# cosv-carrier-teensy40.net
KiCad netlist of a schematic drawn in EAGLE
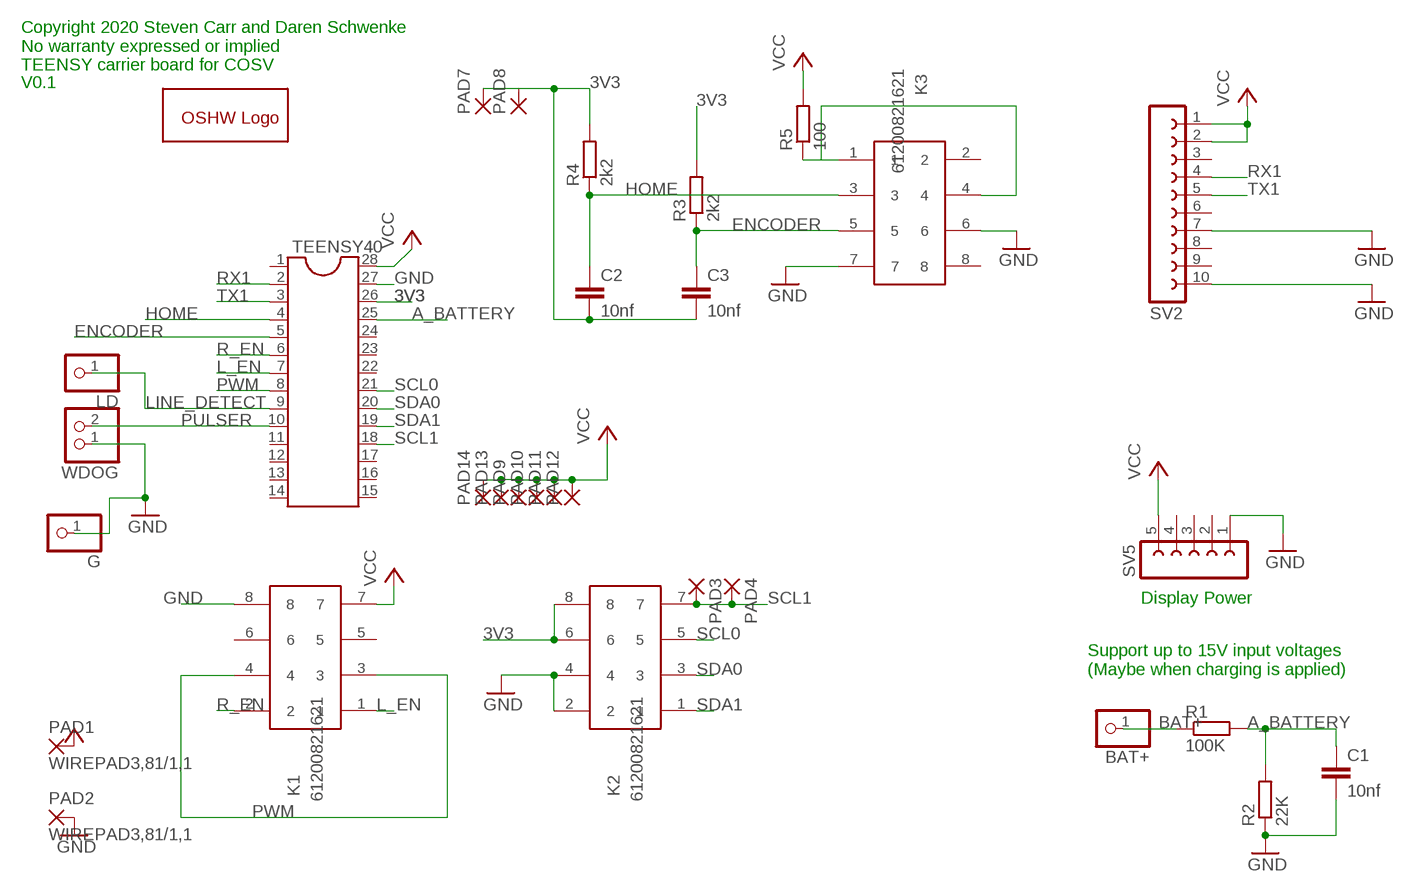
[diagram p0: schematic, sheet 1]

(export (version "E")
  (design (tool "Eeschema 10.0.6"))
  (components
    (comp (ref "BAT+")
      (value "PINHD-1X01_2.54-S")
      (footprint "eagle-import:1X01-S")
      (libsource (lib "eagle-import") (part "PINHD-1X01_2.54-S"))
    )
    (comp (ref "C1")
      (value "10nf")
      (footprint "eagle-import:C1206")
      (libsource (lib "eagle-import") (part "C-EUC1206"))
    )
    (comp (ref "C2")
      (value "10nf")
      (footprint "eagle-import:C1206")
      (libsource (lib "eagle-import") (part "C-EUC1206"))
    )
    (comp (ref "C3")
      (value "10nf")
      (footprint "eagle-import:C1206")
      (libsource (lib "eagle-import") (part "C-EUC1206"))
    )
    (comp (ref "G")
      (value "PINHD-1X01_2.54-S")
      (footprint "eagle-import:1X01-S")
      (libsource (lib "eagle-import") (part "PINHD-1X01_2.54-S"))
    )
    (comp (ref "GOLD_ORB_SM1")
      (value "OSHWLOGOLOGO8MM")
      (footprint "eagle-import:OSHW_8MM")
      (libsource (lib "eagle-import") (part "OSHWLOGOLOGO8MM"))
    )
    (comp (ref "K1")
      (value "61200821621")
      (footprint "eagle-import:61200821621")
      (libsource (lib "eagle-import") (part "61200821621"))
    )
    (comp (ref "K2")
      (value "61200821621")
      (footprint "eagle-import:61200821621")
      (libsource (lib "eagle-import") (part "61200821621"))
    )
    (comp (ref "K3")
      (value "61200821621")
      (footprint "eagle-import:61200821621")
      (libsource (lib "eagle-import") (part "61200821621"))
    )
    (comp (ref "LD")
      (value "PINHD-1X01_2.54-S")
      (footprint "eagle-import:1X01-S")
      (libsource (lib "eagle-import") (part "PINHD-1X01_2.54-S"))
    )
    (comp (ref "PAD1")
      (value "WIREPAD3,81/1,1")
      (footprint "eagle-import:3,81_1,1")
      (libsource (lib "eagle-import") (part "WIREPAD3,81/1,1"))
    )
    (comp (ref "PAD2")
      (value "WIREPAD3,81/1,1")
      (footprint "eagle-import:3,81_1,1")
      (libsource (lib "eagle-import") (part "WIREPAD3,81/1,1"))
    )
    (comp (ref "PAD3")
      (value "1,6/0,9")
      (footprint "eagle-import:1,6_0,9")
      (libsource (lib "eagle-import") (part "1,6/0,9"))
    )
    (comp (ref "PAD4")
      (value "1,6/0,9")
      (footprint "eagle-import:1,6_0,9")
      (libsource (lib "eagle-import") (part "1,6/0,9"))
    )
    (comp (ref "PAD7")
      (value "1,6/0,9")
      (footprint "eagle-import:1,6_0,9")
      (libsource (lib "eagle-import") (part "1,6/0,9"))
    )
    (comp (ref "PAD8")
      (value "1,6/0,9")
      (footprint "eagle-import:1,6_0,9")
      (libsource (lib "eagle-import") (part "1,6/0,9"))
    )
    (comp (ref "PAD9")
      (value "1,6/0,9")
      (footprint "eagle-import:1,6_0,9")
      (libsource (lib "eagle-import") (part "1,6/0,9"))
    )
    (comp (ref "PAD10")
      (value "1,6/0,9")
      (footprint "eagle-import:1,6_0,9")
      (libsource (lib "eagle-import") (part "1,6/0,9"))
    )
    (comp (ref "PAD11")
      (value "1,6/0,9")
      (footprint "eagle-import:1,6_0,9")
      (libsource (lib "eagle-import") (part "1,6/0,9"))
    )
    (comp (ref "PAD12")
      (value "1,6/0,9")
      (footprint "eagle-import:1,6_0,9")
      (libsource (lib "eagle-import") (part "1,6/0,9"))
    )
    (comp (ref "PAD13")
      (value "1,6/0,9")
      (footprint "eagle-import:1,6_0,9")
      (libsource (lib "eagle-import") (part "1,6/0,9"))
    )
    (comp (ref "PAD14")
      (value "1,6/0,9")
      (footprint "eagle-import:1,6_0,9")
      (libsource (lib "eagle-import") (part "1,6/0,9"))
    )
    (comp (ref "R1")
      (value "100K")
      (footprint "eagle-import:R1206")
      (libsource (lib "eagle-import") (part "R-EU_R1206"))
    )
    (comp (ref "R2")
      (value "22K")
      (footprint "eagle-import:R1206")
      (libsource (lib "eagle-import") (part "R-EU_R1206"))
    )
    (comp (ref "R3")
      (value "2k2")
      (footprint "eagle-import:R1206")
      (libsource (lib "eagle-import") (part "R-EU_R1206"))
    )
    (comp (ref "R4")
      (value "2k2")
      (footprint "eagle-import:R1206")
      (libsource (lib "eagle-import") (part "R-EU_R1206"))
    )
    (comp (ref "R5")
      (value "100")
      (footprint "eagle-import:R1206")
      (libsource (lib "eagle-import") (part "R-EU_R1206"))
    )
    (comp (ref "SV2")
      (value "FE10-1")
      (footprint "eagle-import:FE10")
      (libsource (lib "eagle-import") (part "FE10-1"))
    )
    (comp (ref "SV5")
      (value "FE05W")
      (footprint "eagle-import:FE05W")
      (libsource (lib "eagle-import") (part "FE05W"))
    )
    (comp (ref "TEENSY40")
      (value "DIL28")
      (footprint "eagle-import:DIL28-6")
      (libsource (lib "eagle-import") (part "DIL28"))
    )
    (comp (ref "WDOG")
      (value "PINHD-1X2")
      (footprint "eagle-import:1X02")
      (libsource (lib "eagle-import") (part "PINHD-1X2"))
    )
  )
  (nets
    (net (code "1") (name "/3V3") (class "Default")
      (node (ref "C2") (pin "2") (pinfunction "2_2") (pintype "passive"))
      (node (ref "C3") (pin "2") (pinfunction "2_2") (pintype "passive"))
      (node (ref "K2") (pin "6") (pinfunction "6_6") (pintype "passive"))
      (node (ref "K2") (pin "8") (pinfunction "8_8") (pintype "passive"))
      (node (ref "PAD7") (pin "1") (pinfunction "P_1") (pintype "passive"))
      (node (ref "PAD8") (pin "1") (pinfunction "P_1") (pintype "passive"))
      (node (ref "R3") (pin "2") (pinfunction "2_2") (pintype "passive"))
      (node (ref "R4") (pin "2") (pinfunction "2_2") (pintype "passive"))
      (node (ref "TEENSY40") (pin "26") (pinfunction "26_26") (pintype "passive"))
    )
    (net (code "2") (name "/A_BATTERY") (class "Default")
      (node (ref "C1") (pin "1") (pinfunction "1_1") (pintype "passive"))
      (node (ref "R1") (pin "2") (pinfunction "2_2") (pintype "passive"))
      (node (ref "R2") (pin "2") (pinfunction "2_2") (pintype "passive"))
      (node (ref "TEENSY40") (pin "25") (pinfunction "25_25") (pintype "passive"))
    )
    (net (code "3") (name "/BAT+") (class "Default")
      (node (ref "BAT+") (pin "1") (pinfunction "1_1") (pintype "passive"))
      (node (ref "R1") (pin "1") (pinfunction "1_1") (pintype "passive"))
    )
    (net (code "4") (name "/ENCODER") (class "Default")
      (node (ref "C3") (pin "1") (pinfunction "1_1") (pintype "passive"))
      (node (ref "K3") (pin "5") (pinfunction "5_5") (pintype "passive"))
      (node (ref "R3") (pin "1") (pinfunction "1_1") (pintype "passive"))
      (node (ref "TEENSY40") (pin "5") (pinfunction "5_5") (pintype "passive"))
    )
    (net (code "5") (name "/HOME") (class "Default")
      (node (ref "C2") (pin "1") (pinfunction "1_1") (pintype "passive"))
      (node (ref "K3") (pin "3") (pinfunction "3_3") (pintype "passive"))
      (node (ref "R4") (pin "1") (pinfunction "1_1") (pintype "passive"))
      (node (ref "TEENSY40") (pin "4") (pinfunction "4_4") (pintype "passive"))
    )
    (net (code "6") (name "/LINE_DETECT") (class "Default")
      (node (ref "LD") (pin "1") (pinfunction "1_1") (pintype "passive"))
      (node (ref "TEENSY40") (pin "9") (pinfunction "9_9") (pintype "passive"))
    )
    (net (code "7") (name "/L_EN") (class "Default")
      (node (ref "K1") (pin "1") (pinfunction "1_1") (pintype "passive"))
      (node (ref "TEENSY40") (pin "7") (pinfunction "7_7") (pintype "passive"))
    )
    (net (code "8") (name "/PULSER") (class "Default")
      (node (ref "TEENSY40") (pin "10") (pinfunction "10_10") (pintype "passive"))
      (node (ref "WDOG") (pin "2") (pinfunction "2_2") (pintype "passive"))
    )
    (net (code "9") (name "/PWM") (class "Default")
      (node (ref "K1") (pin "3") (pinfunction "3_3") (pintype "passive"))
      (node (ref "K1") (pin "4") (pinfunction "4_4") (pintype "passive"))
      (node (ref "TEENSY40") (pin "8") (pinfunction "8_8") (pintype "passive"))
    )
    (net (code "10") (name "/RX1") (class "Default")
      (node (ref "SV2") (pin "4") (pinfunction "4_4") (pintype "passive"))
      (node (ref "TEENSY40") (pin "2") (pinfunction "2_2") (pintype "passive"))
    )
    (net (code "11") (name "/R_EN") (class "Default")
      (node (ref "K1") (pin "2") (pinfunction "2_2") (pintype "passive"))
      (node (ref "TEENSY40") (pin "6") (pinfunction "6_6") (pintype "passive"))
    )
    (net (code "12") (name "/SCL0") (class "Default")
      (node (ref "K2") (pin "5") (pinfunction "5_5") (pintype "passive"))
      (node (ref "TEENSY40") (pin "21") (pinfunction "21_21") (pintype "passive"))
    )
    (net (code "13") (name "/SCL1") (class "Default")
      (node (ref "K2") (pin "7") (pinfunction "7_7") (pintype "passive"))
      (node (ref "PAD3") (pin "1") (pinfunction "P_1") (pintype "passive"))
      (node (ref "PAD4") (pin "1") (pinfunction "P_1") (pintype "passive"))
      (node (ref "TEENSY40") (pin "18") (pinfunction "18_18") (pintype "passive"))
    )
    (net (code "14") (name "/SDA0") (class "Default")
      (node (ref "K2") (pin "3") (pinfunction "3_3") (pintype "passive"))
      (node (ref "TEENSY40") (pin "20") (pinfunction "20_20") (pintype "passive"))
    )
    (net (code "15") (name "/SDA1") (class "Default")
      (node (ref "K2") (pin "1") (pinfunction "1_1") (pintype "passive"))
      (node (ref "TEENSY40") (pin "19") (pinfunction "19_19") (pintype "passive"))
    )
    (net (code "16") (name "/TX1") (class "Default")
      (node (ref "SV2") (pin "5") (pinfunction "5_5") (pintype "passive"))
      (node (ref "TEENSY40") (pin "3") (pinfunction "3_3") (pintype "passive"))
    )
    (net (code "17") (name "GND") (class "Default")
      (node (ref "C1") (pin "2") (pinfunction "2_2") (pintype "passive"))
      (node (ref "G") (pin "1") (pinfunction "1_1") (pintype "passive"))
      (node (ref "K1") (pin "8") (pinfunction "8_8") (pintype "passive"))
      (node (ref "K2") (pin "2") (pinfunction "2_2") (pintype "passive"))
      (node (ref "K2") (pin "4") (pinfunction "4_4") (pintype "passive"))
      (node (ref "K3") (pin "6") (pinfunction "6_6") (pintype "passive"))
      (node (ref "K3") (pin "7") (pinfunction "7_7") (pintype "passive"))
      (node (ref "PAD2") (pin "1") (pinfunction "P_1") (pintype "passive"))
      (node (ref "R2") (pin "1") (pinfunction "1_1") (pintype "passive"))
      (node (ref "SV2") (pin "10") (pinfunction "10_10") (pintype "passive"))
      (node (ref "SV2") (pin "7") (pinfunction "7_7") (pintype "passive"))
      (node (ref "SV5") (pin "1") (pinfunction "1_1") (pintype "passive"))
      (node (ref "TEENSY40") (pin "27") (pinfunction "27_27") (pintype "passive"))
      (node (ref "WDOG") (pin "1") (pinfunction "1_1") (pintype "passive"))
    )
    (net (code "18") (name "Net-(K3-Pad1)") (class "Default")
      (node (ref "K3") (pin "1") (pinfunction "1_1") (pintype "passive"))
      (node (ref "K3") (pin "4") (pinfunction "4_4") (pintype "passive"))
      (node (ref "R5") (pin "1") (pinfunction "1_1") (pintype "passive"))
    )
    (net (code "19") (name "VCC") (class "Default")
      (node (ref "K1") (pin "7") (pinfunction "7_7") (pintype "passive"))
      (node (ref "PAD1") (pin "1") (pinfunction "P_1") (pintype "passive"))
      (node (ref "PAD10") (pin "1") (pinfunction "P_1") (pintype "passive"))
      (node (ref "PAD11") (pin "1") (pinfunction "P_1") (pintype "passive"))
      (node (ref "PAD12") (pin "1") (pinfunction "P_1") (pintype "passive"))
      (node (ref "PAD13") (pin "1") (pinfunction "P_1") (pintype "passive"))
      (node (ref "PAD14") (pin "1") (pinfunction "P_1") (pintype "passive"))
      (node (ref "PAD9") (pin "1") (pinfunction "P_1") (pintype "passive"))
      (node (ref "R5") (pin "2") (pinfunction "2_2") (pintype "passive"))
      (node (ref "SV2") (pin "1") (pinfunction "1_1") (pintype "passive"))
      (node (ref "SV2") (pin "2") (pinfunction "2_2") (pintype "passive"))
      (node (ref "SV5") (pin "5") (pinfunction "5_5") (pintype "passive"))
      (node (ref "TEENSY40") (pin "28") (pinfunction "28_28") (pintype "passive"))
    )
    (net (code "20") (name "unconnected-(K1-Pad5)") (class "Default")
      (node (ref "K1") (pin "5") (pinfunction "5_5") (pintype "passive"))
    )
    (net (code "21") (name "unconnected-(K1-Pad6)") (class "Default")
      (node (ref "K1") (pin "6") (pinfunction "6_6") (pintype "passive"))
    )
    (net (code "22") (name "unconnected-(K3-Pad2)") (class "Default")
      (node (ref "K3") (pin "2") (pinfunction "2_2") (pintype "passive"))
    )
    (net (code "23") (name "unconnected-(K3-Pad8)") (class "Default")
      (node (ref "K3") (pin "8") (pinfunction "8_8") (pintype "passive"))
    )
    (net (code "24") (name "unconnected-(SV2-Pad3)") (class "Default")
      (node (ref "SV2") (pin "3") (pinfunction "3_3") (pintype "passive"))
    )
    (net (code "25") (name "unconnected-(SV2-Pad6)") (class "Default")
      (node (ref "SV2") (pin "6") (pinfunction "6_6") (pintype "passive"))
    )
    (net (code "26") (name "unconnected-(SV2-Pad8)") (class "Default")
      (node (ref "SV2") (pin "8") (pinfunction "8_8") (pintype "passive"))
    )
    (net (code "27") (name "unconnected-(SV2-Pad9)") (class "Default")
      (node (ref "SV2") (pin "9") (pinfunction "9_9") (pintype "passive"))
    )
    (net (code "28") (name "unconnected-(SV5-Pad2)") (class "Default")
      (node (ref "SV5") (pin "2") (pinfunction "2_2") (pintype "passive"))
    )
    (net (code "29") (name "unconnected-(SV5-Pad3)") (class "Default")
      (node (ref "SV5") (pin "3") (pinfunction "3_3") (pintype "passive"))
    )
    (net (code "30") (name "unconnected-(SV5-Pad4)") (class "Default")
      (node (ref "SV5") (pin "4") (pinfunction "4_4") (pintype "passive"))
    )
    (net (code "31") (name "unconnected-(TEENSY40-Pad1)") (class "Default")
      (node (ref "TEENSY40") (pin "1") (pinfunction "1_1") (pintype "passive"))
    )
    (net (code "32") (name "unconnected-(TEENSY40-Pad11)") (class "Default")
      (node (ref "TEENSY40") (pin "11") (pinfunction "11_11") (pintype "passive"))
    )
    (net (code "33") (name "unconnected-(TEENSY40-Pad12)") (class "Default")
      (node (ref "TEENSY40") (pin "12") (pinfunction "12_12") (pintype "passive"))
    )
    (net (code "34") (name "unconnected-(TEENSY40-Pad13)") (class "Default")
      (node (ref "TEENSY40") (pin "13") (pinfunction "13_13") (pintype "passive"))
    )
    (net (code "35") (name "unconnected-(TEENSY40-Pad14)") (class "Default")
      (node (ref "TEENSY40") (pin "14") (pinfunction "14_14") (pintype "passive"))
    )
    (net (code "36") (name "unconnected-(TEENSY40-Pad15)") (class "Default")
      (node (ref "TEENSY40") (pin "15") (pinfunction "15_15") (pintype "passive"))
    )
    (net (code "37") (name "unconnected-(TEENSY40-Pad16)") (class "Default")
      (node (ref "TEENSY40") (pin "16") (pinfunction "16_16") (pintype "passive"))
    )
    (net (code "38") (name "unconnected-(TEENSY40-Pad17)") (class "Default")
      (node (ref "TEENSY40") (pin "17") (pinfunction "17_17") (pintype "passive"))
    )
    (net (code "39") (name "unconnected-(TEENSY40-Pad22)") (class "Default")
      (node (ref "TEENSY40") (pin "22") (pinfunction "22_22") (pintype "passive"))
    )
    (net (code "40") (name "unconnected-(TEENSY40-Pad23)") (class "Default")
      (node (ref "TEENSY40") (pin "23") (pinfunction "23_23") (pintype "passive"))
    )
    (net (code "41") (name "unconnected-(TEENSY40-Pad24)") (class "Default")
      (node (ref "TEENSY40") (pin "24") (pinfunction "24_24") (pintype "passive"))
    )
  )
)
